# screw_and_Hole.net
KiCad netlist of a schematic drawn in Altium Designer
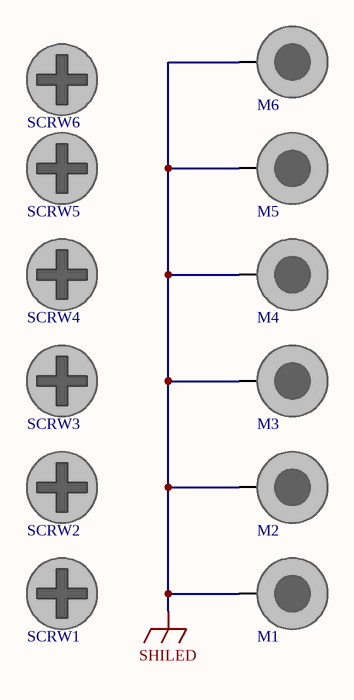
[diagram p0: screw and Hole.SchDoc]

(export (version "E")
  (design (tool "Eeschema 10.0.6"))
  (components
    (comp (ref "M1")
      (value "DNP/MH")
      (footprint "SCMH_M3")
      (description "SCREW mouting, M3, 3.0mm diameter and 6.0mm PanHead")
      (libsource (lib "mech_mountingHole") (part "SCMH_M3"))
    )
    (comp (ref "M2")
      (value "DNP/MH")
      (footprint "SCMH_M3")
      (description "SCREW mouting, M3, 3.0mm diameter and 6.0mm PanHead")
      (libsource (lib "mech_mountingHole") (part "SCMH_M3"))
    )
    (comp (ref "M3")
      (value "DNP/MH")
      (footprint "SCMH_M3")
      (description "SCREW mouting, M3, 3.0mm diameter and 6.0mm PanHead")
      (libsource (lib "mech_mountingHole") (part "SCMH_M3"))
    )
    (comp (ref "M4")
      (value "DNP/MH")
      (footprint "SCMH_M3")
      (description "SCREW mouting, M3, 3.0mm diameter and 6.0mm PanHead")
      (libsource (lib "mech_mountingHole") (part "SCMH_M3"))
    )
    (comp (ref "M5")
      (value "DNP/MH")
      (footprint "SCMH_M3")
      (description "SCREW mouting, M3, 3.0mm diameter and 6.0mm PanHead")
      (libsource (lib "mech_mountingHole") (part "SCMH_M3"))
    )
    (comp (ref "M6")
      (value "DNP/MH")
      (footprint "SCMH_M3")
      (description "SCREW mouting, M3, 3.0mm diameter and 6.0mm PanHead")
      (libsource (lib "mech_mountingHole") (part "SCMH_M3"))
    )
    (comp (ref "SCRW1")
      (value "SCREW")
      (footprint "SCRW_PANH_PHLIPS_M3X5")
      (description "SCREW, M3, 3.0mm diameter and 6.0mm PanHead")
      (libsource (lib "mech_mountingHole") (part "SCRW_PANH_PHLIPS_M3X5"))
    )
    (comp (ref "SCRW2")
      (value "SCREW")
      (footprint "SCRW_PANH_PHLIPS_M3X5")
      (description "SCREW, M3, 3.0mm diameter and 6.0mm PanHead")
      (libsource (lib "mech_mountingHole") (part "SCRW_PANH_PHLIPS_M3X5"))
    )
    (comp (ref "SCRW3")
      (value "SCREW")
      (footprint "SCRW_PANH_PHLIPS_M3X5")
      (description "SCREW, M3, 3.0mm diameter and 6.0mm PanHead")
      (libsource (lib "mech_mountingHole") (part "SCRW_PANH_PHLIPS_M3X5"))
    )
    (comp (ref "SCRW4")
      (value "SCREW")
      (footprint "SCRW_PANH_PHLIPS_M3X5")
      (description "SCREW, M3, 3.0mm diameter and 6.0mm PanHead")
      (libsource (lib "mech_mountingHole") (part "SCRW_PANH_PHLIPS_M3X5"))
    )
    (comp (ref "SCRW5")
      (value "SCREW")
      (footprint "SCRW_PANH_PHLIPS_M3X5")
      (description "SCREW, M3, 3.0mm diameter and 6.0mm PanHead")
      (libsource (lib "mech_mountingHole") (part "SCRW_PANH_PHLIPS_M3X5"))
    )
    (comp (ref "SCRW6")
      (value "SCREW")
      (footprint "SCRW_PANH_PHLIPS_M3X5")
      (description "SCREW, M3, 3.0mm diameter and 6.0mm PanHead")
      (libsource (lib "mech_mountingHole") (part "SCRW_PANH_PHLIPS_M3X5"))
    )
  )
  (nets
    (net (code "1") (name "SHILED") (class "Default")
      (node (ref "M1") (pin "1") (pinfunction "1_1") (pintype "passive"))
      (node (ref "M2") (pin "1") (pinfunction "1_1") (pintype "passive"))
      (node (ref "M3") (pin "1") (pinfunction "1_1") (pintype "passive"))
      (node (ref "M4") (pin "1") (pinfunction "1_1") (pintype "passive"))
      (node (ref "M5") (pin "1") (pinfunction "1_1") (pintype "passive"))
      (node (ref "M6") (pin "1") (pinfunction "1_1") (pintype "passive"))
    )
  )
)
